# T-LOG_v2_0.net
KiCad netlist of a schematic drawn in Altium Designer
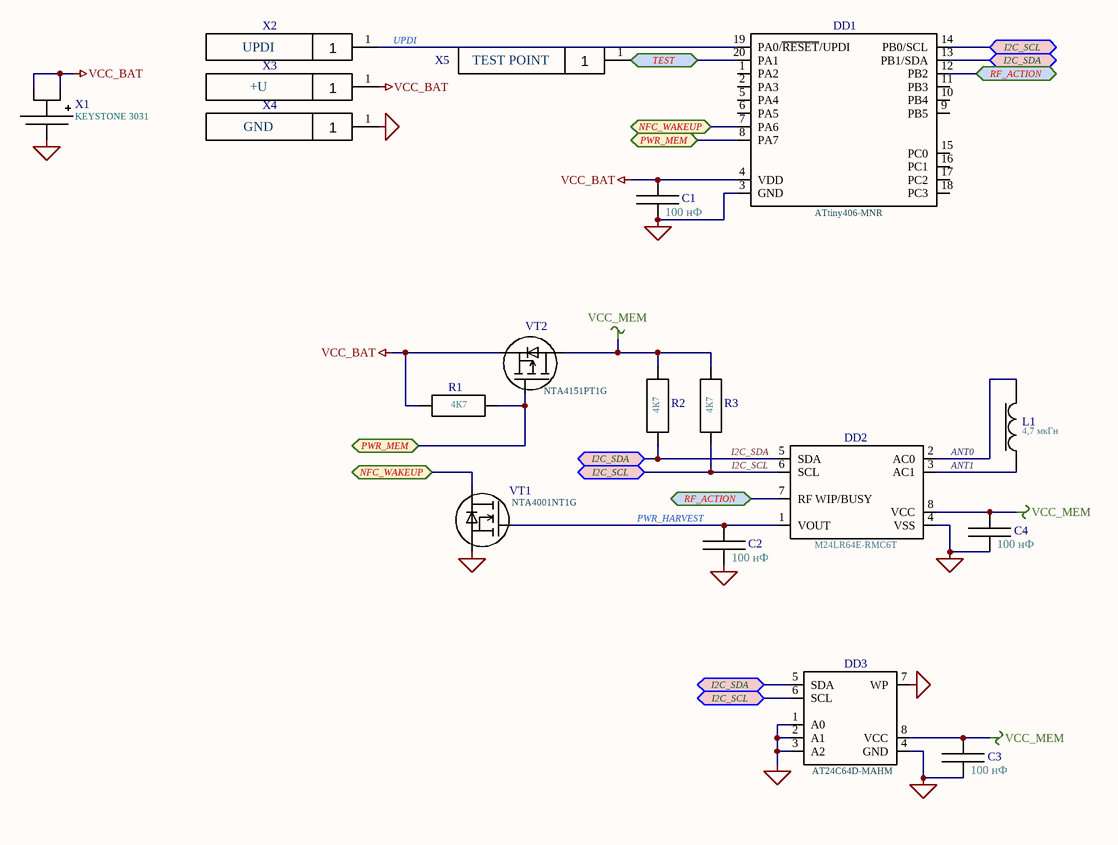
[diagram p0: T-LOG v2.0.SchDoc]

(export (version "E")
  (design (tool "Eeschema 10.0.6"))
  (components
    (comp (ref "C1")
      (value "100 нФ")
      (footprint "C0402")
      (description "Чип-конденсатор 0,1 мкФ 50 В 0402")
      (libsource (lib "RC") (part "C0402"))
    )
    (comp (ref "C2")
      (value "100 нФ")
      (footprint "C0402")
      (description "Чип-конденсатор 0,1 мкФ 50 В 0402")
      (libsource (lib "RC") (part "C0402"))
    )
    (comp (ref "C3")
      (value "100 нФ")
      (footprint "C0402")
      (description "Чип-конденсатор 0,1 мкФ 50 В 0402")
      (libsource (lib "RC") (part "C0402"))
    )
    (comp (ref "C4")
      (value "100 нФ")
      (footprint "C0402")
      (description "Чип-конденсатор 0,1 мкФ 50 В 0402")
      (libsource (lib "RC") (part "C0402"))
    )
    (comp (ref "DD1")
      (value "ATtiny406-MNR")
      (footprint "VQFN20_3x3_0.4")
      (description "Микроконтроллер AVR ATtiny406-MNR VQFN20")
      (libsource (lib "MCU") (part "ATtiny406-MNR"))
    )
    (comp (ref "DD2")
      (value "M24LR64E-RMC6T")
      (footprint "UDFN-8_2X3")
      (description "Память EEPROM I2C/NFC 64Кбит M24LR64E-RMC6T UFDFN8 ST")
      (libsource (lib "MEMORY") (part "M24LR64E-RMC6T"))
    )
    (comp (ref "DD3")
      (value "AT24C64D-MAHM")
      (footprint "UDFN-8_2X3")
      (description "Память EEPROM I2C 64 Кбит AT24C64D‑MAHM UDFN8")
      (libsource (lib "MEMORY") (part "AT24C64D-MAHM"))
    )
    (comp (ref "L1")
      (value "4,7 мкГн")
      (footprint "WE-LQ_1210")
      (description "Чип-индуктивность WE-LQ 744032004 4,7 мкГн 0,49 А Wurth Elektronik")
      (libsource (lib "ZX") (part "WE-LQ_744032004"))
    )
    (comp (ref "R1")
      (value "4К7")
      (footprint "R0402")
      (description "Чип-резистор 4,7 кОм 5% 0402")
      (libsource (lib "RC") (part "R0402"))
    )
    (comp (ref "R2")
      (value "4К7")
      (footprint "R0402")
      (description "Чип-резистор 4,7 кОм 5% 0402")
      (libsource (lib "RC") (part "R0402"))
    )
    (comp (ref "R3")
      (value "4К7")
      (footprint "R0402")
      (description "Чип-резистор 4,7 кОм 5% 0402")
      (libsource (lib "RC") (part "R0402"))
    )
    (comp (ref "VT1")
      (value "NTA4001NT1G")
      (footprint "SC-75")
      (description "Транзистор MOSFET N-Channel NTA4001NT1G")
      (libsource (lib "SEMICONDUCTORS") (part "NTA4001NT1G"))
    )
    (comp (ref "VT2")
      (value "NTA4151PT1G")
      (footprint "SC-75")
      (description "Транзистор MOSFET P-Channel NTA4151PT1G")
      (libsource (lib "SEMICONDUCTORS") (part "NTA4151PT1G"))
    )
    (comp (ref "X1")
      (value "KEYSTONE 3031")
      (footprint "KEYSTONE_3031")
      (description "Держатель элемента CR1025 KEYSTONE 3031")
      (libsource (lib "CONNECTORS") (part "KEYSTONE_3031"))
    )
    (comp (ref "X2")
      (value "VIA_0.5x1x2_RECTANGLE")
      (footprint "VIA_0.5x1x2_RECTANGLE")
      (libsource (lib "CONNECTORS") (part "VIA_0.5x1x2_RECTANGLE"))
    )
    (comp (ref "X3")
      (value "VIA_0.5x1x2_RECTANGLE")
      (footprint "VIA_0.5x1x2_RECTANGLE")
      (libsource (lib "CONNECTORS") (part "VIA_0.5x1x2_RECTANGLE"))
    )
    (comp (ref "X4")
      (value "VIA_0.5x1x2_RECTANGLE")
      (footprint "VIA_0.5x1x2_RECTANGLE")
      (libsource (lib "CONNECTORS") (part "VIA_0.5x1x2_RECTANGLE"))
    )
    (comp (ref "X5")
      (value "VIA_0.5x1x2_RECTANGLE")
      (footprint "VIA_0.5x1x2_RECTANGLE")
      (libsource (lib "CONNECTORS") (part "VIA_0.5x1x2_RECTANGLE"))
    )
  )
  (nets
    (net (code "1") (name "/ANT0") (class "Default")
      (node (ref "DD2") (pin "2") (pinfunction "AC0_2") (pintype "passive"))
      (node (ref "L1") (pin "2") (pinfunction "2_2") (pintype "passive"))
    )
    (net (code "2") (name "/ANT1") (class "Default")
      (node (ref "DD2") (pin "3") (pinfunction "AC1_3") (pintype "passive"))
      (node (ref "L1") (pin "1") (pinfunction "1_1") (pintype "passive"))
    )
    (net (code "3") (name "/I2C_SCL") (class "Default")
      (node (ref "DD1") (pin "14") (pinfunction "PB0/SCL_14") (pintype "passive"))
      (node (ref "DD2") (pin "6") (pinfunction "SCL_6") (pintype "passive"))
      (node (ref "DD3") (pin "6") (pinfunction "SCL_6") (pintype "passive"))
      (node (ref "R3") (pin "1") (pinfunction "1_1") (pintype "passive"))
    )
    (net (code "4") (name "/I2C_SDA") (class "Default")
      (node (ref "DD1") (pin "13") (pinfunction "PB1/SDA_13") (pintype "passive"))
      (node (ref "DD2") (pin "5") (pinfunction "SDA_5") (pintype "passive"))
      (node (ref "DD3") (pin "5") (pinfunction "SDA_5") (pintype "passive"))
      (node (ref "R2") (pin "1") (pinfunction "1_1") (pintype "passive"))
    )
    (net (code "5") (name "/NFC_WAKEUP") (class "Default")
      (node (ref "DD1") (pin "7") (pinfunction "PA6_7") (pintype "passive"))
      (node (ref "VT1") (pin "3") (pinfunction "D_3") (pintype "passive"))
    )
    (net (code "6") (name "/PWR_HARVEST") (class "Default")
      (node (ref "C2") (pin "2") (pinfunction "2_2") (pintype "passive"))
      (node (ref "DD2") (pin "1") (pinfunction "VOUT_1") (pintype "passive"))
      (node (ref "VT1") (pin "1") (pinfunction "G_1") (pintype "passive"))
    )
    (net (code "7") (name "/PWR_MEM") (class "Default")
      (node (ref "DD1") (pin "8") (pinfunction "PA7_8") (pintype "passive"))
      (node (ref "R1") (pin "1") (pinfunction "1_1") (pintype "passive"))
      (node (ref "VT2") (pin "1") (pinfunction "G_1") (pintype "passive"))
    )
    (net (code "8") (name "/RF_ACTION") (class "Default")
      (node (ref "DD1") (pin "12") (pinfunction "PB2_12") (pintype "passive"))
      (node (ref "DD2") (pin "7") (pinfunction "RF_WIP/BUSY_7") (pintype "passive"))
    )
    (net (code "9") (name "/TEST") (class "Default")
      (node (ref "DD1") (pin "20") (pinfunction "PA1_20") (pintype "passive"))
      (node (ref "X5") (pin "1") (pinfunction "1_1") (pintype "passive"))
    )
    (net (code "10") (name "/UPDI") (class "Default")
      (node (ref "DD1") (pin "19") (pinfunction "PA0/~{RESET}/UPDI_19") (pintype "passive"))
      (node (ref "X2") (pin "1") (pinfunction "1_1") (pintype "passive"))
    )
    (net (code "11") (name "GND") (class "Default")
      (node (ref "C1") (pin "1") (pinfunction "1_1") (pintype "passive"))
      (node (ref "C2") (pin "1") (pinfunction "1_1") (pintype "passive"))
      (node (ref "C3") (pin "1") (pinfunction "1_1") (pintype "passive"))
      (node (ref "C4") (pin "1") (pinfunction "1_1") (pintype "passive"))
      (node (ref "DD1") (pin "3") (pinfunction "GND_3") (pintype "passive"))
      (node (ref "DD2") (pin "4") (pinfunction "VSS_4") (pintype "passive"))
      (node (ref "DD3") (pin "1") (pinfunction "A0_1") (pintype "passive"))
      (node (ref "DD3") (pin "2") (pinfunction "A1_2") (pintype "passive"))
      (node (ref "DD3") (pin "3") (pinfunction "A2_3") (pintype "passive"))
      (node (ref "DD3") (pin "4") (pinfunction "GND_4") (pintype "passive"))
      (node (ref "DD3") (pin "7") (pinfunction "WP_7") (pintype "passive"))
      (node (ref "VT1") (pin "2") (pinfunction "S_2") (pintype "passive"))
      (node (ref "X1") (pin "3") (pinfunction "3_3") (pintype "passive"))
      (node (ref "X4") (pin "1") (pinfunction "1_1") (pintype "passive"))
    )
    (net (code "12") (name "VCC_BAT") (class "Default")
      (node (ref "C1") (pin "2") (pinfunction "2_2") (pintype "passive"))
      (node (ref "DD1") (pin "4") (pinfunction "VDD_4") (pintype "passive"))
      (node (ref "R1") (pin "2") (pinfunction "2_2") (pintype "passive"))
      (node (ref "VT2") (pin "2") (pinfunction "S_2") (pintype "passive"))
      (node (ref "X1") (pin "1") (pinfunction "1_1") (pintype "passive"))
      (node (ref "X1") (pin "2") (pinfunction "2_2") (pintype "passive"))
      (node (ref "X3") (pin "1") (pinfunction "1_1") (pintype "passive"))
    )
    (net (code "13") (name "VCC_MEM") (class "Default")
      (node (ref "C3") (pin "2") (pinfunction "2_2") (pintype "passive"))
      (node (ref "C4") (pin "2") (pinfunction "2_2") (pintype "passive"))
      (node (ref "DD2") (pin "8") (pinfunction "VCC_8") (pintype "passive"))
      (node (ref "DD3") (pin "8") (pinfunction "VCC_8") (pintype "passive"))
      (node (ref "R2") (pin "2") (pinfunction "2_2") (pintype "passive"))
      (node (ref "R3") (pin "2") (pinfunction "2_2") (pintype "passive"))
      (node (ref "VT2") (pin "3") (pinfunction "D_3") (pintype "passive"))
    )
    (net (code "14") (name "unconnected-(DD1-PA2-Pad1)") (class "Default")
      (node (ref "DD1") (pin "1") (pinfunction "PA2_1") (pintype "passive"))
    )
    (net (code "15") (name "unconnected-(DD1-PA3-Pad2)") (class "Default")
      (node (ref "DD1") (pin "2") (pinfunction "PA3_2") (pintype "passive"))
    )
    (net (code "16") (name "unconnected-(DD1-PA4-Pad5)") (class "Default")
      (node (ref "DD1") (pin "5") (pinfunction "PA4_5") (pintype "passive"))
    )
    (net (code "17") (name "unconnected-(DD1-PA5-Pad6)") (class "Default")
      (node (ref "DD1") (pin "6") (pinfunction "PA5_6") (pintype "passive"))
    )
    (net (code "18") (name "unconnected-(DD1-PB3-Pad11)") (class "Default")
      (node (ref "DD1") (pin "11") (pinfunction "PB3_11") (pintype "passive"))
    )
    (net (code "19") (name "unconnected-(DD1-PB4-Pad10)") (class "Default")
      (node (ref "DD1") (pin "10") (pinfunction "PB4_10") (pintype "passive"))
    )
    (net (code "20") (name "unconnected-(DD1-PB5-Pad9)") (class "Default")
      (node (ref "DD1") (pin "9") (pinfunction "PB5_9") (pintype "passive"))
    )
    (net (code "21") (name "unconnected-(DD1-PC0-Pad15)") (class "Default")
      (node (ref "DD1") (pin "15") (pinfunction "PC0_15") (pintype "passive"))
    )
    (net (code "22") (name "unconnected-(DD1-PC1-Pad16)") (class "Default")
      (node (ref "DD1") (pin "16") (pinfunction "PC1_16") (pintype "passive"))
    )
    (net (code "23") (name "unconnected-(DD1-PC2-Pad17)") (class "Default")
      (node (ref "DD1") (pin "17") (pinfunction "PC2_17") (pintype "passive"))
    )
    (net (code "24") (name "unconnected-(DD1-PC3-Pad18)") (class "Default")
      (node (ref "DD1") (pin "18") (pinfunction "PC3_18") (pintype "passive"))
    )
  )
)
